# Power.net
KiCad netlist of a schematic drawn in Altium Designer
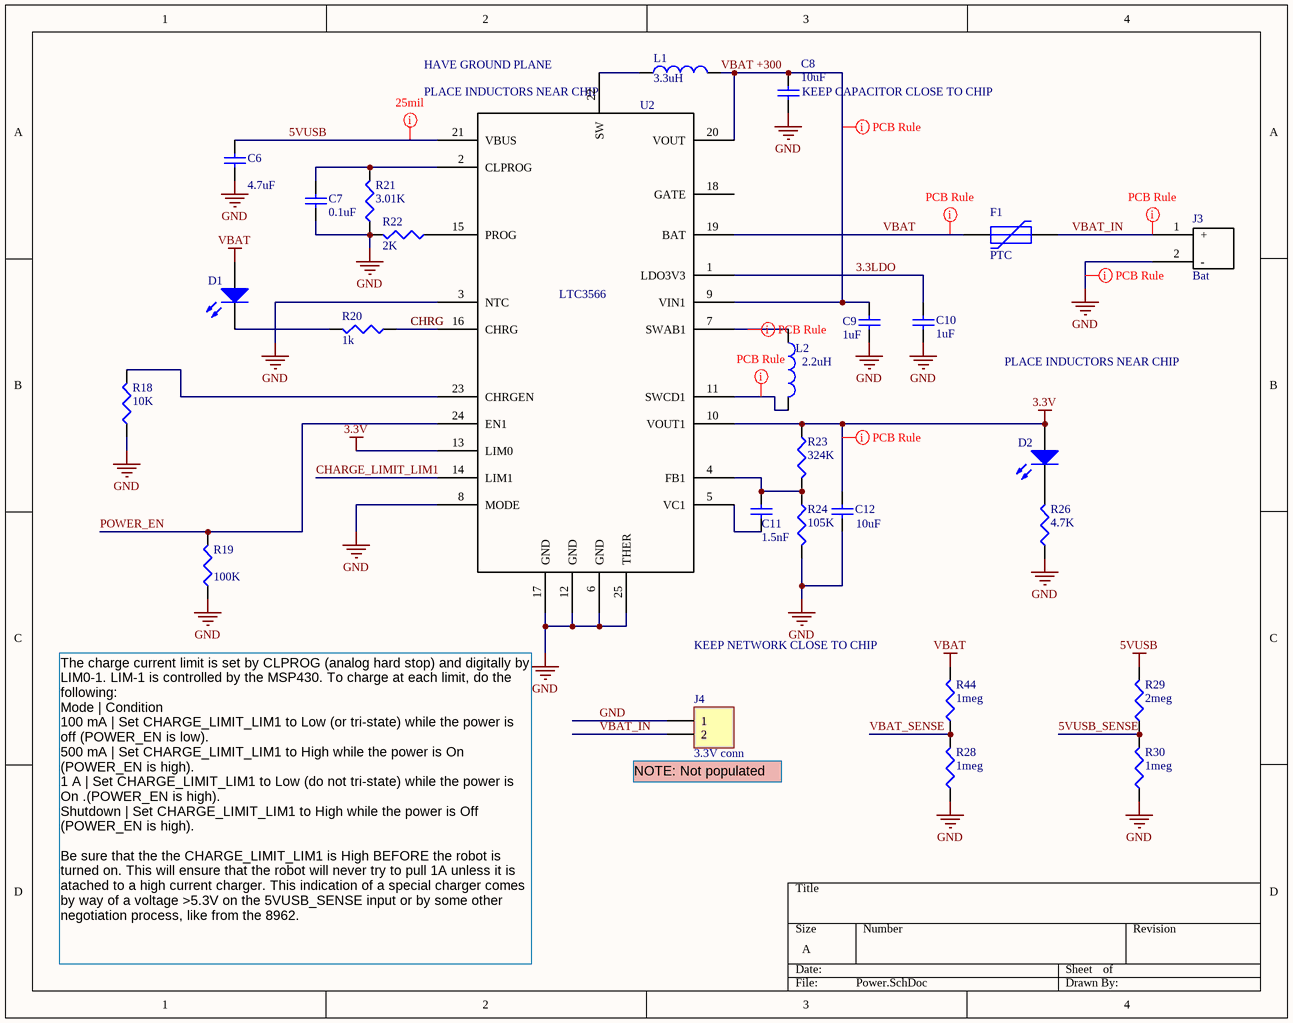
[diagram p0: Power.SchDoc]

(export (version "E")
  (design (tool "Eeschema 10.0.6"))
  (components
    (comp (ref "C6")
      (value "4.7uF")
      (footprint "CAPC1608L")
      (description "Capacitor (Semiconductor SIM Model)")
      (fields (field (name "Comment") "Cap Semi") (field (name "PUBLISHER") "Altium Limited"))
      (libsource (lib "Miscellaneous Devices") (part "Cap Semi"))
    )
    (comp (ref "C7")
      (value "0.1uF")
      (footprint "CAPC1005L")
      (description "Capacitor")
      (fields (field (name "Comment") "Cap") (field (name "PUBLISHER") "Altium Limited"))
      (libsource (lib "Miscellaneous Devices") (part "Cap"))
    )
    (comp (ref "C8")
      (value "10uF")
      (footprint "CAPC1608L")
      (description "Capacitor")
      (fields (field (name "Comment") "Cap") (field (name "PUBLISHER") "Altium Limited"))
      (libsource (lib "Miscellaneous Devices") (part "Cap"))
    )
    (comp (ref "C9")
      (value "1uF")
      (footprint "CAPC1608L")
      (description "Capacitor")
      (fields (field (name "Comment") "Cap") (field (name "PUBLISHER") "Altium Limited"))
      (libsource (lib "Miscellaneous Devices") (part "Cap"))
    )
    (comp (ref "C10")
      (value "1uF")
      (footprint "CAPC1608L")
      (description "Capacitor")
      (fields (field (name "Comment") "Cap") (field (name "PUBLISHER") "Altium Limited"))
      (libsource (lib "Miscellaneous Devices") (part "Cap"))
    )
    (comp (ref "C11")
      (value "1.5nF")
      (footprint "CAPC1005L")
      (description "Capacitor")
      (fields (field (name "Comment") "Cap") (field (name "PUBLISHER") "Altium Limited"))
      (libsource (lib "Miscellaneous Devices") (part "Cap"))
    )
    (comp (ref "C12")
      (value "10uF")
      (footprint "CAPC1608L")
      (description "Capacitor")
      (fields (field (name "Comment") "Cap") (field (name "PUBLISHER") "Altium Limited"))
      (libsource (lib "Miscellaneous Devices") (part "Cap"))
    )
    (comp (ref "D1")
      (value "Charge")
      (footprint "INDC2012L")
      (description "Typical RED, GREEN, YELLOW, AMBER GaAs LED")
      (fields (field (name "PUBLISHER") "Altium Limited"))
      (libsource (lib "Miscellaneous Devices") (part "LED2"))
    )
    (comp (ref "D2")
      (value "Power")
      (footprint "INDC2012L")
      (description "Typical RED, GREEN, YELLOW, AMBER GaAs LED")
      (fields (field (name "PUBLISHER") "Altium Limited"))
      (libsource (lib "Miscellaneous Devices") (part "LED2"))
    )
    (comp (ref "F1")
      (value "PTC")
      (footprint "ERJ8G-1206")
      (description "Fuse")
      (fields (field (name "PUBLISHER") "Altium Limited"))
      (libsource (lib "mrone") (part "PTC_FUSE"))
    )
    (comp (ref "J3")
      (value "Bat")
      (footprint "BatteryConnJST")
      (libsource (lib "mrone") (part "BatteryConnJST"))
    )
    (comp (ref "J4")
      (value "3.3V conn")
      (footprint "HDR1X2")
      (description "Header, 2-Pin")
      (fields (field (name "PUBLISHER") "Altium Limited"))
      (libsource (lib "Miscellaneous Connectors") (part "Header 2"))
    )
    (comp (ref "L1") (value "3.3uH") (footprint "IndPow") (libsource (lib "mrone") (part "Inductor")))
    (comp (ref "L2") (value "2.2uH") (footprint "IndPow") (libsource (lib "mrone") (part "Inductor")))
    (comp (ref "R18")
      (value "10K")
      (footprint "RESC1608L")
      (description "Resistor")
      (fields (field (name "Comment") "Res3") (field (name "PUBLISHER") "Altium Limited"))
      (libsource (lib "Miscellaneous Devices") (part "Res3"))
    )
    (comp (ref "R19")
      (value "100K")
      (footprint "RESC1608L")
      (description "Resistor")
      (fields (field (name "Comment") "Res3") (field (name "PUBLISHER") "Altium Limited"))
      (libsource (lib "Miscellaneous Devices") (part "Res3"))
    )
    (comp (ref "R20")
      (value "1k")
      (footprint "RESC1608L")
      (description "Resistor")
      (fields (field (name "Comment") "Res3") (field (name "PUBLISHER") "Altium Limited"))
      (libsource (lib "Miscellaneous Devices") (part "Res3"))
    )
    (comp (ref "R21")
      (value "3.01K")
      (footprint "RESC1608L")
      (description "Resistor")
      (fields (field (name "Comment") "Res3") (field (name "PUBLISHER") "Altium Limited"))
      (libsource (lib "Miscellaneous Devices") (part "Res3"))
    )
    (comp (ref "R22")
      (value "2K")
      (footprint "RESC1608L")
      (description "Resistor")
      (fields (field (name "Comment") "Res3") (field (name "PUBLISHER") "Altium Limited"))
      (libsource (lib "Miscellaneous Devices") (part "Res3"))
    )
    (comp (ref "R23")
      (value "324K")
      (footprint "RESC1608L")
      (description "Resistor")
      (fields (field (name "Comment") "Res3") (field (name "PUBLISHER") "Altium Limited"))
      (libsource (lib "Miscellaneous Devices") (part "Res3"))
    )
    (comp (ref "R24")
      (value "105K")
      (footprint "RESC1608L")
      (description "Resistor")
      (fields (field (name "Comment") "Res3") (field (name "PUBLISHER") "Altium Limited"))
      (libsource (lib "Miscellaneous Devices") (part "Res3"))
    )
    (comp (ref "R26")
      (value "4.7K")
      (footprint "RESC1608L")
      (description "Resistor")
      (fields (field (name "Comment") "Res3") (field (name "PUBLISHER") "Altium Limited"))
      (libsource (lib "Miscellaneous Devices") (part "Res3"))
    )
    (comp (ref "R28")
      (value "1meg")
      (footprint "RESC1608L")
      (description "Resistor")
      (fields (field (name "Comment") "Res3") (field (name "PUBLISHER") "Altium Limited"))
      (libsource (lib "Miscellaneous Devices") (part "Res3"))
    )
    (comp (ref "R29")
      (value "2meg")
      (footprint "RESC1608L")
      (description "Resistor")
      (fields (field (name "Comment") "Res3") (field (name "PUBLISHER") "Altium Limited"))
      (libsource (lib "Miscellaneous Devices") (part "Res3"))
    )
    (comp (ref "R30")
      (value "1meg")
      (footprint "RESC1608L")
      (description "Resistor")
      (fields (field (name "Comment") "Res3") (field (name "PUBLISHER") "Altium Limited"))
      (libsource (lib "Miscellaneous Devices") (part "Res3"))
    )
    (comp (ref "R44")
      (value "1meg")
      (footprint "RESC1608L")
      (description "Resistor")
      (fields (field (name "Comment") "Res3") (field (name "PUBLISHER") "Altium Limited"))
      (libsource (lib "Miscellaneous Devices") (part "Res3"))
    )
    (comp (ref "U2")
      (value "LTC3566")
      (footprint "QFN-24")
      (libsource (lib "Schematic Components") (part "LTC3566"))
    )
  )
  (nets
    (net (code "1") (name "/3.3LDO") (class "Default")
      (node (ref "C10") (pin "1") (pinfunction "1_1") (pintype "passive"))
      (node (ref "U2") (pin "1") (pinfunction "LDO3V3_1") (pintype "passive"))
    )
    (net (code "2") (name "/5VUSB_SENSE") (class "Default")
      (node (ref "R29") (pin "1") (pinfunction "1_1") (pintype "passive"))
      (node (ref "R30") (pin "2") (pinfunction "2_2") (pintype "passive"))
    )
    (net (code "3") (name "/CHARGE_LIMIT_LIM1") (class "Default")
      (node (ref "U2") (pin "14") (pinfunction "LIM1_14") (pintype "passive"))
    )
    (net (code "4") (name "/CHRG") (class "Default")
      (node (ref "R20") (pin "1") (pinfunction "1_1") (pintype "passive"))
      (node (ref "U2") (pin "16") (pinfunction "CHRG_16") (pintype "passive"))
    )
    (net (code "5") (name "/POWER_EN") (class "Default")
      (node (ref "R19") (pin "2") (pinfunction "2_2") (pintype "passive"))
      (node (ref "U2") (pin "24") (pinfunction "EN1_24") (pintype "passive"))
    )
    (net (code "6") (name "/VBAT +300") (class "Default")
      (node (ref "C8") (pin "2") (pinfunction "2_2") (pintype "passive"))
      (node (ref "C9") (pin "1") (pinfunction "1_1") (pintype "passive"))
      (node (ref "L1") (pin "2") (pinfunction "2_2") (pintype "passive"))
      (node (ref "U2") (pin "20") (pinfunction "VOUT_20") (pintype "passive"))
      (node (ref "U2") (pin "9") (pinfunction "VIN1_9") (pintype "passive"))
    )
    (net (code "7") (name "/VBAT_IN") (class "Default")
      (node (ref "F1") (pin "2") (pinfunction "2_2") (pintype "passive"))
      (node (ref "J3") (pin "1") (pinfunction "+_1") (pintype "passive"))
      (node (ref "J4") (pin "2") (pinfunction "2_2") (pintype "passive"))
    )
    (net (code "8") (name "/VBAT_SENSE") (class "Default")
      (node (ref "R28") (pin "2") (pinfunction "2_2") (pintype "passive"))
      (node (ref "R44") (pin "1") (pinfunction "1_1") (pintype "passive"))
    )
    (net (code "9") (name "3.3V") (class "Default")
      (node (ref "C12") (pin "2") (pinfunction "2_2") (pintype "passive"))
      (node (ref "D2") (pin "1") (pinfunction "A_1") (pintype "passive"))
      (node (ref "R23") (pin "1") (pinfunction "1_1") (pintype "passive"))
      (node (ref "U2") (pin "10") (pinfunction "VOUT1_10") (pintype "passive"))
      (node (ref "U2") (pin "13") (pinfunction "LIM0_13") (pintype "passive"))
    )
    (net (code "10") (name "5VUSB") (class "Default")
      (node (ref "C6") (pin "2") (pinfunction "2_2") (pintype "passive"))
      (node (ref "R29") (pin "2") (pinfunction "2_2") (pintype "passive"))
      (node (ref "U2") (pin "21") (pinfunction "VBUS_21") (pintype "passive"))
    )
    (net (code "11") (name "GND") (class "Default")
      (node (ref "C10") (pin "2") (pinfunction "2_2") (pintype "passive"))
      (node (ref "C12") (pin "1") (pinfunction "1_1") (pintype "passive"))
      (node (ref "C6") (pin "1") (pinfunction "1_1") (pintype "passive"))
      (node (ref "C7") (pin "1") (pinfunction "1_1") (pintype "passive"))
      (node (ref "C8") (pin "1") (pinfunction "1_1") (pintype "passive"))
      (node (ref "C9") (pin "2") (pinfunction "2_2") (pintype "passive"))
      (node (ref "J3") (pin "2") (pinfunction "-_2") (pintype "passive"))
      (node (ref "J4") (pin "1") (pinfunction "1_1") (pintype "passive"))
      (node (ref "R18") (pin "1") (pinfunction "1_1") (pintype "passive"))
      (node (ref "R19") (pin "1") (pinfunction "1_1") (pintype "passive"))
      (node (ref "R21") (pin "1") (pinfunction "1_1") (pintype "passive"))
      (node (ref "R22") (pin "2") (pinfunction "2_2") (pintype "passive"))
      (node (ref "R24") (pin "2") (pinfunction "2_2") (pintype "passive"))
      (node (ref "R26") (pin "1") (pinfunction "1_1") (pintype "passive"))
      (node (ref "R28") (pin "1") (pinfunction "1_1") (pintype "passive"))
      (node (ref "R30") (pin "1") (pinfunction "1_1") (pintype "passive"))
      (node (ref "U2") (pin "12") (pinfunction "GND_12") (pintype "passive"))
      (node (ref "U2") (pin "17") (pinfunction "GND_17") (pintype "passive"))
      (node (ref "U2") (pin "25") (pinfunction "THER_25") (pintype "passive"))
      (node (ref "U2") (pin "3") (pinfunction "NTC_3") (pintype "passive"))
      (node (ref "U2") (pin "6") (pinfunction "GND_6") (pintype "passive"))
      (node (ref "U2") (pin "8") (pinfunction "MODE_8") (pintype "passive"))
    )
    (net (code "12") (name "Net-(D1-K)") (class "Default")
      (node (ref "D1") (pin "2") (pinfunction "K_2") (pintype "passive"))
      (node (ref "R20") (pin "2") (pinfunction "2_2") (pintype "passive"))
    )
    (net (code "13") (name "Net-(D2-K)") (class "Default")
      (node (ref "D2") (pin "2") (pinfunction "K_2") (pintype "passive"))
      (node (ref "R26") (pin "2") (pinfunction "2_2") (pintype "passive"))
    )
    (net (code "14") (name "Net-(U2-CHRGEN)") (class "Default")
      (node (ref "R18") (pin "2") (pinfunction "2_2") (pintype "passive"))
      (node (ref "U2") (pin "23") (pinfunction "CHRGEN_23") (pintype "passive"))
    )
    (net (code "15") (name "Net-(U2-CLPROG)") (class "Default")
      (node (ref "C7") (pin "2") (pinfunction "2_2") (pintype "passive"))
      (node (ref "R21") (pin "2") (pinfunction "2_2") (pintype "passive"))
      (node (ref "U2") (pin "2") (pinfunction "CLPROG_2") (pintype "passive"))
    )
    (net (code "16") (name "Net-(U2-FB1)") (class "Default")
      (node (ref "C11") (pin "1") (pinfunction "1_1") (pintype "passive"))
      (node (ref "R23") (pin "2") (pinfunction "2_2") (pintype "passive"))
      (node (ref "R24") (pin "1") (pinfunction "1_1") (pintype "passive"))
      (node (ref "U2") (pin "4") (pinfunction "FB1_4") (pintype "passive"))
    )
    (net (code "17") (name "Net-(U2-PROG)") (class "Default")
      (node (ref "R22") (pin "1") (pinfunction "1_1") (pintype "passive"))
      (node (ref "U2") (pin "15") (pinfunction "PROG_15") (pintype "passive"))
    )
    (net (code "18") (name "Net-(U2-SW)") (class "Default")
      (node (ref "L1") (pin "1") (pinfunction "1_1") (pintype "passive"))
      (node (ref "U2") (pin "22") (pinfunction "SW_22") (pintype "passive"))
    )
    (net (code "19") (name "Net-(U2-SWAB1)") (class "Default")
      (node (ref "L2") (pin "1") (pinfunction "1_1") (pintype "passive"))
      (node (ref "U2") (pin "7") (pinfunction "SWAB1_7") (pintype "passive"))
    )
    (net (code "20") (name "Net-(U2-SWCD1)") (class "Default")
      (node (ref "L2") (pin "2") (pinfunction "2_2") (pintype "passive"))
      (node (ref "U2") (pin "11") (pinfunction "SWCD1_11") (pintype "passive"))
    )
    (net (code "21") (name "Net-(U2-VC1)") (class "Default")
      (node (ref "C11") (pin "2") (pinfunction "2_2") (pintype "passive"))
      (node (ref "U2") (pin "5") (pinfunction "VC1_5") (pintype "passive"))
    )
    (net (code "22") (name "VBAT") (class "Default")
      (node (ref "D1") (pin "1") (pinfunction "A_1") (pintype "passive"))
      (node (ref "F1") (pin "1") (pinfunction "1_1") (pintype "passive"))
      (node (ref "R44") (pin "2") (pinfunction "2_2") (pintype "passive"))
      (node (ref "U2") (pin "19") (pinfunction "BAT_19") (pintype "passive"))
    )
    (net (code "23") (name "unconnected-(U2-GATE-Pad18)") (class "Default")
      (node (ref "U2") (pin "18") (pinfunction "GATE_18") (pintype "passive"))
    )
  )
)
